# Power_Supply_2_Andrew_editted.net
KiCad netlist of a schematic drawn in EAGLE
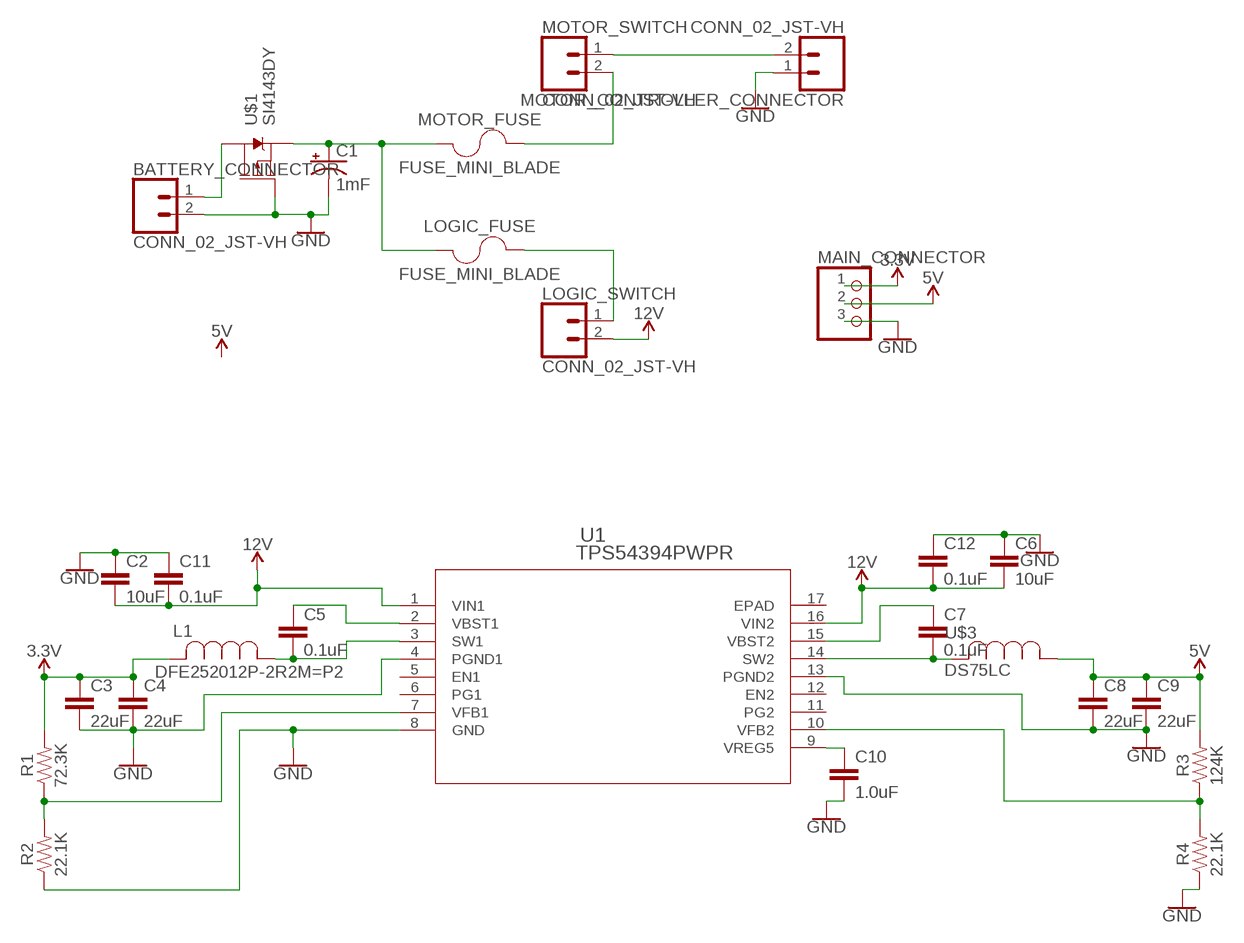
[diagram p0: schematic, sheet 1]

(export (version "E")
  (design (tool "Eeschema 10.0.6"))
  (components
    (comp (ref "BATTERY_CONNECTOR")
      (value "CONN_02_JST-VH")
      (footprint "eagle-import:B2P-VH")
      (libsource (lib "eagle-import") (part "CONN_02_JST-VH"))
    )
    (comp (ref "C1")
      (value "1mF")
      (footprint "eagle-import:CPOL-RADIAL-5MM-10MM")
      (libsource (lib "eagle-import") (part "1000UF-RADIAL-5MM-25V-20%"))
    )
    (comp (ref "C2")
      (value "10uF")
      (footprint "eagle-import:0805")
      (libsource (lib "eagle-import") (part "10UF-0805-10V-10%"))
    )
    (comp (ref "C3")
      (value "22uF")
      (footprint "eagle-import:0805")
      (libsource (lib "eagle-import") (part "22UF-0805-6.3V-20%"))
    )
    (comp (ref "C4")
      (value "22uF")
      (footprint "eagle-import:0805")
      (libsource (lib "eagle-import") (part "22UF-0805-6.3V-20%"))
    )
    (comp (ref "C5")
      (value "0.1uF")
      (footprint "eagle-import:0603")
      (libsource (lib "eagle-import") (part "0.1UF-0603-25V-5%"))
    )
    (comp (ref "C6")
      (value "10uF")
      (footprint "eagle-import:0805")
      (libsource (lib "eagle-import") (part "10UF-0805-10V-10%"))
    )
    (comp (ref "C7")
      (value "0.1uF")
      (footprint "eagle-import:0603")
      (libsource (lib "eagle-import") (part "0.1UF-0603-25V-5%"))
    )
    (comp (ref "C8")
      (value "22uF")
      (footprint "eagle-import:0805")
      (libsource (lib "eagle-import") (part "22UF-0805-6.3V-20%"))
    )
    (comp (ref "C9")
      (value "22uF")
      (footprint "eagle-import:0805")
      (libsource (lib "eagle-import") (part "22UF-0805-6.3V-20%"))
    )
    (comp (ref "C10")
      (value "1.0uF")
      (footprint "eagle-import:0805")
      (libsource (lib "eagle-import") (part "1.0UF-0805-25V-10%"))
    )
    (comp (ref "C11")
      (value "0.1uF")
      (footprint "eagle-import:0603")
      (libsource (lib "eagle-import") (part "0.1UF-0603-25V-5%"))
    )
    (comp (ref "C12")
      (value "0.1uF")
      (footprint "eagle-import:0603")
      (libsource (lib "eagle-import") (part "0.1UF-0603-25V-5%"))
    )
    (comp (ref "L1")
      (value "DFE252012P-2R2M=P2")
      (footprint "eagle-import:DFE252012P-1R0M=P2")
      (fields (field (name "MANUFACTURER_PART_NUMBER") "DFE252012P2R2M=P2"))
      (libsource (lib "eagle-import") (part "DFE252012P-2R2M=P2"))
    )
    (comp (ref "LOGIC_FUSE")
      (value "FUSE_MINI_BLADE")
      (footprint "eagle-import:SL-1538")
      (libsource (lib "eagle-import") (part "FUSE_MINI_BLADE"))
    )
    (comp (ref "LOGIC_SWITCH")
      (value "CONN_02_JST-VH")
      (footprint "eagle-import:B2P-VH")
      (libsource (lib "eagle-import") (part "CONN_02_JST-VH"))
    )
    (comp (ref "MAIN_CONNECTOR")
      (value "PINHD-1X3")
      (footprint "eagle-import:1X03")
      (libsource (lib "eagle-import") (part "PINHD-1X3"))
    )
    (comp (ref "MOTOR_CONTROLLER_CONNECTOR")
      (value "CONN_02_JST-VH")
      (footprint "eagle-import:B2P-VH")
      (libsource (lib "eagle-import") (part "CONN_02_JST-VH"))
    )
    (comp (ref "MOTOR_FUSE")
      (value "FUSE_MINI_BLADE")
      (footprint "eagle-import:SL-1538")
      (libsource (lib "eagle-import") (part "FUSE_MINI_BLADE"))
    )
    (comp (ref "MOTOR_SWITCH")
      (value "CONN_02_JST-VH")
      (footprint "eagle-import:B2P-VH")
      (libsource (lib "eagle-import") (part "CONN_02_JST-VH"))
    )
    (comp (ref "R1")
      (value "72.3K")
      (footprint "eagle-import:0603")
      (libsource (lib "eagle-import") (part "75KOHM-0603-1/10W-1%"))
    )
    (comp (ref "R2")
      (value "22.1K")
      (footprint "eagle-import:0603")
      (libsource (lib "eagle-import") (part "75KOHM-0603-1/10W-1%"))
    )
    (comp (ref "R3")
      (value "124K")
      (footprint "eagle-import:0603")
      (libsource (lib "eagle-import") (part "75KOHM-0603-1/10W-1%"))
    )
    (comp (ref "R4")
      (value "22.1K")
      (footprint "eagle-import:0603")
      (libsource (lib "eagle-import") (part "75KOHM-0603-1/10W-1%"))
    )
    (comp (ref "U$1")
      (value "SI4143DY")
      (footprint "eagle-import:SO-8")
      (libsource (lib "eagle-import") (part "SI4143DY"))
    )
    (comp (ref "U$3")
      (value "DS75LC")
      (footprint "eagle-import:DS75LC")
      (libsource (lib "eagle-import") (part "DS75LC"))
    )
    (comp (ref "U1")
      (value "TPS54394PWPR")
      (footprint "eagle-import:PWP16_3P4X2P46")
      (libsource (lib "eagle-import") (part "TPS54394PWPR"))
    )
  )
  (nets
    (net (code "1") (name "3.3V") (class "Default")
      (node (ref "C3") (pin "1") (pinfunction "1_1") (pintype "passive"))
      (node (ref "C4") (pin "1") (pinfunction "1_1") (pintype "passive"))
      (node (ref "L1") (pin "2") (pinfunction "2_2") (pintype "passive"))
      (node (ref "MAIN_CONNECTOR") (pin "1") (pinfunction "1_1") (pintype "passive"))
      (node (ref "R1") (pin "2") (pinfunction "2_2") (pintype "passive"))
    )
    (net (code "2") (name "5V") (class "Default")
      (node (ref "C8") (pin "1") (pinfunction "1_1") (pintype "passive"))
      (node (ref "C9") (pin "1") (pinfunction "1_1") (pintype "passive"))
      (node (ref "MAIN_CONNECTOR") (pin "2") (pinfunction "2_2") (pintype "passive"))
      (node (ref "R3") (pin "2") (pinfunction "2_2") (pintype "passive"))
      (node (ref "U$3") (pin "P$1") (pinfunction "1_P$1") (pintype "passive"))
    )
    (net (code "3") (name "12V") (class "Default")
      (node (ref "C11") (pin "2") (pinfunction "2_2") (pintype "passive"))
      (node (ref "C12") (pin "2") (pinfunction "2_2") (pintype "passive"))
      (node (ref "C2") (pin "2") (pinfunction "2_2") (pintype "passive"))
      (node (ref "C6") (pin "2") (pinfunction "2_2") (pintype "passive"))
      (node (ref "LOGIC_SWITCH") (pin "2") (pinfunction "2_2") (pintype "passive"))
      (node (ref "U1") (pin "1") (pinfunction "VIN1_1") (pintype "input"))
      (node (ref "U1") (pin "16") (pinfunction "VIN2_16") (pintype "input"))
    )
    (net (code "4") (name "GND") (class "Default")
      (node (ref "BATTERY_CONNECTOR") (pin "2") (pinfunction "2_2") (pintype "passive"))
      (node (ref "C1") (pin "-") (pinfunction "-_-") (pintype "passive"))
      (node (ref "C10") (pin "2") (pinfunction "2_2") (pintype "passive"))
      (node (ref "C11") (pin "1") (pinfunction "1_1") (pintype "passive"))
      (node (ref "C12") (pin "1") (pinfunction "1_1") (pintype "passive"))
      (node (ref "C2") (pin "1") (pinfunction "1_1") (pintype "passive"))
      (node (ref "C3") (pin "2") (pinfunction "2_2") (pintype "passive"))
      (node (ref "C4") (pin "2") (pinfunction "2_2") (pintype "passive"))
      (node (ref "C6") (pin "1") (pinfunction "1_1") (pintype "passive"))
      (node (ref "C8") (pin "2") (pinfunction "2_2") (pintype "passive"))
      (node (ref "C9") (pin "2") (pinfunction "2_2") (pintype "passive"))
      (node (ref "MAIN_CONNECTOR") (pin "3") (pinfunction "3_3") (pintype "passive"))
      (node (ref "MOTOR_CONTROLLER_CONNECTOR") (pin "1") (pinfunction "1_1") (pintype "passive"))
      (node (ref "R2") (pin "1") (pinfunction "1_1") (pintype "passive"))
      (node (ref "R4") (pin "1") (pinfunction "1_1") (pintype "passive"))
      (node (ref "U$1") (pin "4") (pinfunction "G_4") (pintype "bidirectional"))
      (node (ref "U1") (pin "13") (pinfunction "PGND2_13") (pintype "bidirectional"))
      (node (ref "U1") (pin "4") (pinfunction "PGND1_4") (pintype "power_in"))
      (node (ref "U1") (pin "8") (pinfunction "GND_8") (pintype "bidirectional"))
    )
    (net (code "5") (name "Net-(BATTERY_CONNECTOR-Pad1)") (class "Default")
      (node (ref "BATTERY_CONNECTOR") (pin "1") (pinfunction "1_1") (pintype "passive"))
      (node (ref "U$1") (pin "5") (pinfunction "D_5") (pintype "bidirectional"))
      (node (ref "U$1") (pin "6") (pinfunction "D_6") (pintype "bidirectional"))
      (node (ref "U$1") (pin "7") (pinfunction "D_7") (pintype "bidirectional"))
      (node (ref "U$1") (pin "8") (pinfunction "D_8") (pintype "bidirectional"))
    )
    (net (code "6") (name "Net-(LOGIC_FUSE-1)") (class "Default")
      (node (ref "C1") (pin "+") (pinfunction "+_+") (pintype "passive"))
      (node (ref "LOGIC_FUSE") (pin "P$1") (pinfunction "1_P$1") (pintype "bidirectional"))
      (node (ref "MOTOR_FUSE") (pin "P$1") (pinfunction "1_P$1") (pintype "bidirectional"))
      (node (ref "U$1") (pin "1") (pinfunction "S_1") (pintype "bidirectional"))
      (node (ref "U$1") (pin "2") (pinfunction "S_2") (pintype "bidirectional"))
      (node (ref "U$1") (pin "3") (pinfunction "S_3") (pintype "bidirectional"))
    )
    (net (code "7") (name "Net-(LOGIC_FUSE-2)") (class "Default")
      (node (ref "LOGIC_FUSE") (pin "P$2") (pinfunction "2_P$2") (pintype "bidirectional"))
      (node (ref "LOGIC_SWITCH") (pin "1") (pinfunction "1_1") (pintype "passive"))
    )
    (net (code "8") (name "Net-(MOTOR_CONTROLLER_CONNECTOR-Pad2)") (class "Default")
      (node (ref "MOTOR_CONTROLLER_CONNECTOR") (pin "2") (pinfunction "2_2") (pintype "passive"))
      (node (ref "MOTOR_SWITCH") (pin "1") (pinfunction "1_1") (pintype "passive"))
    )
    (net (code "9") (name "Net-(MOTOR_FUSE-2)") (class "Default")
      (node (ref "MOTOR_FUSE") (pin "P$2") (pinfunction "2_P$2") (pintype "bidirectional"))
      (node (ref "MOTOR_SWITCH") (pin "2") (pinfunction "2_2") (pintype "passive"))
    )
    (net (code "10") (name "Net-(U$3-2)") (class "Default")
      (node (ref "C7") (pin "2") (pinfunction "2_2") (pintype "passive"))
      (node (ref "U$3") (pin "P$2") (pinfunction "2_P$2") (pintype "passive"))
      (node (ref "U1") (pin "14") (pinfunction "SW2_14") (pintype "bidirectional"))
    )
    (net (code "11") (name "Net-(U1-SW1)") (class "Default")
      (node (ref "C5") (pin "2") (pinfunction "2_2") (pintype "passive"))
      (node (ref "L1") (pin "1") (pinfunction "1_1") (pintype "passive"))
      (node (ref "U1") (pin "3") (pinfunction "SW1_3") (pintype "bidirectional"))
    )
    (net (code "12") (name "Net-(U1-VBST1)") (class "Default")
      (node (ref "C5") (pin "1") (pinfunction "1_1") (pintype "passive"))
      (node (ref "U1") (pin "2") (pinfunction "VBST1_2") (pintype "input"))
    )
    (net (code "13") (name "Net-(U1-VBST2)") (class "Default")
      (node (ref "C7") (pin "1") (pinfunction "1_1") (pintype "passive"))
      (node (ref "U1") (pin "15") (pinfunction "VBST2_15") (pintype "input"))
    )
    (net (code "14") (name "Net-(U1-VFB1)") (class "Default")
      (node (ref "R1") (pin "1") (pinfunction "1_1") (pintype "passive"))
      (node (ref "R2") (pin "2") (pinfunction "2_2") (pintype "passive"))
      (node (ref "U1") (pin "7") (pinfunction "VFB1_7") (pintype "input"))
    )
    (net (code "15") (name "Net-(U1-VFB2)") (class "Default")
      (node (ref "R3") (pin "1") (pinfunction "1_1") (pintype "passive"))
      (node (ref "R4") (pin "2") (pinfunction "2_2") (pintype "passive"))
      (node (ref "U1") (pin "10") (pinfunction "VFB2_10") (pintype "input"))
    )
    (net (code "16") (name "Net-(U1-VREG5)") (class "Default")
      (node (ref "C10") (pin "1") (pinfunction "1_1") (pintype "passive"))
      (node (ref "U1") (pin "9") (pinfunction "VREG5_9") (pintype "output"))
    )
    (net (code "17") (name "unconnected-(U1-EN1-Pad5)") (class "Default")
      (node (ref "U1") (pin "5") (pinfunction "EN1_5") (pintype "input"))
    )
    (net (code "18") (name "unconnected-(U1-EN2-Pad12)") (class "Default")
      (node (ref "U1") (pin "12") (pinfunction "EN2_12") (pintype "input"))
    )
    (net (code "19") (name "unconnected-(U1-EPAD-Pad17)") (class "Default")
      (node (ref "U1") (pin "17") (pinfunction "EPAD_17") (pintype "passive"))
    )
    (net (code "20") (name "unconnected-(U1-PG1-Pad6)") (class "Default")
      (node (ref "U1") (pin "6") (pinfunction "PG1_6") (pintype "output"))
    )
    (net (code "21") (name "unconnected-(U1-PG2-Pad11)") (class "Default")
      (node (ref "U1") (pin "11") (pinfunction "PG2_11") (pintype "output"))
    )
  )
)
